# mm8_D016Aoshw.net
KiCad netlist of a schematic drawn in EAGLE
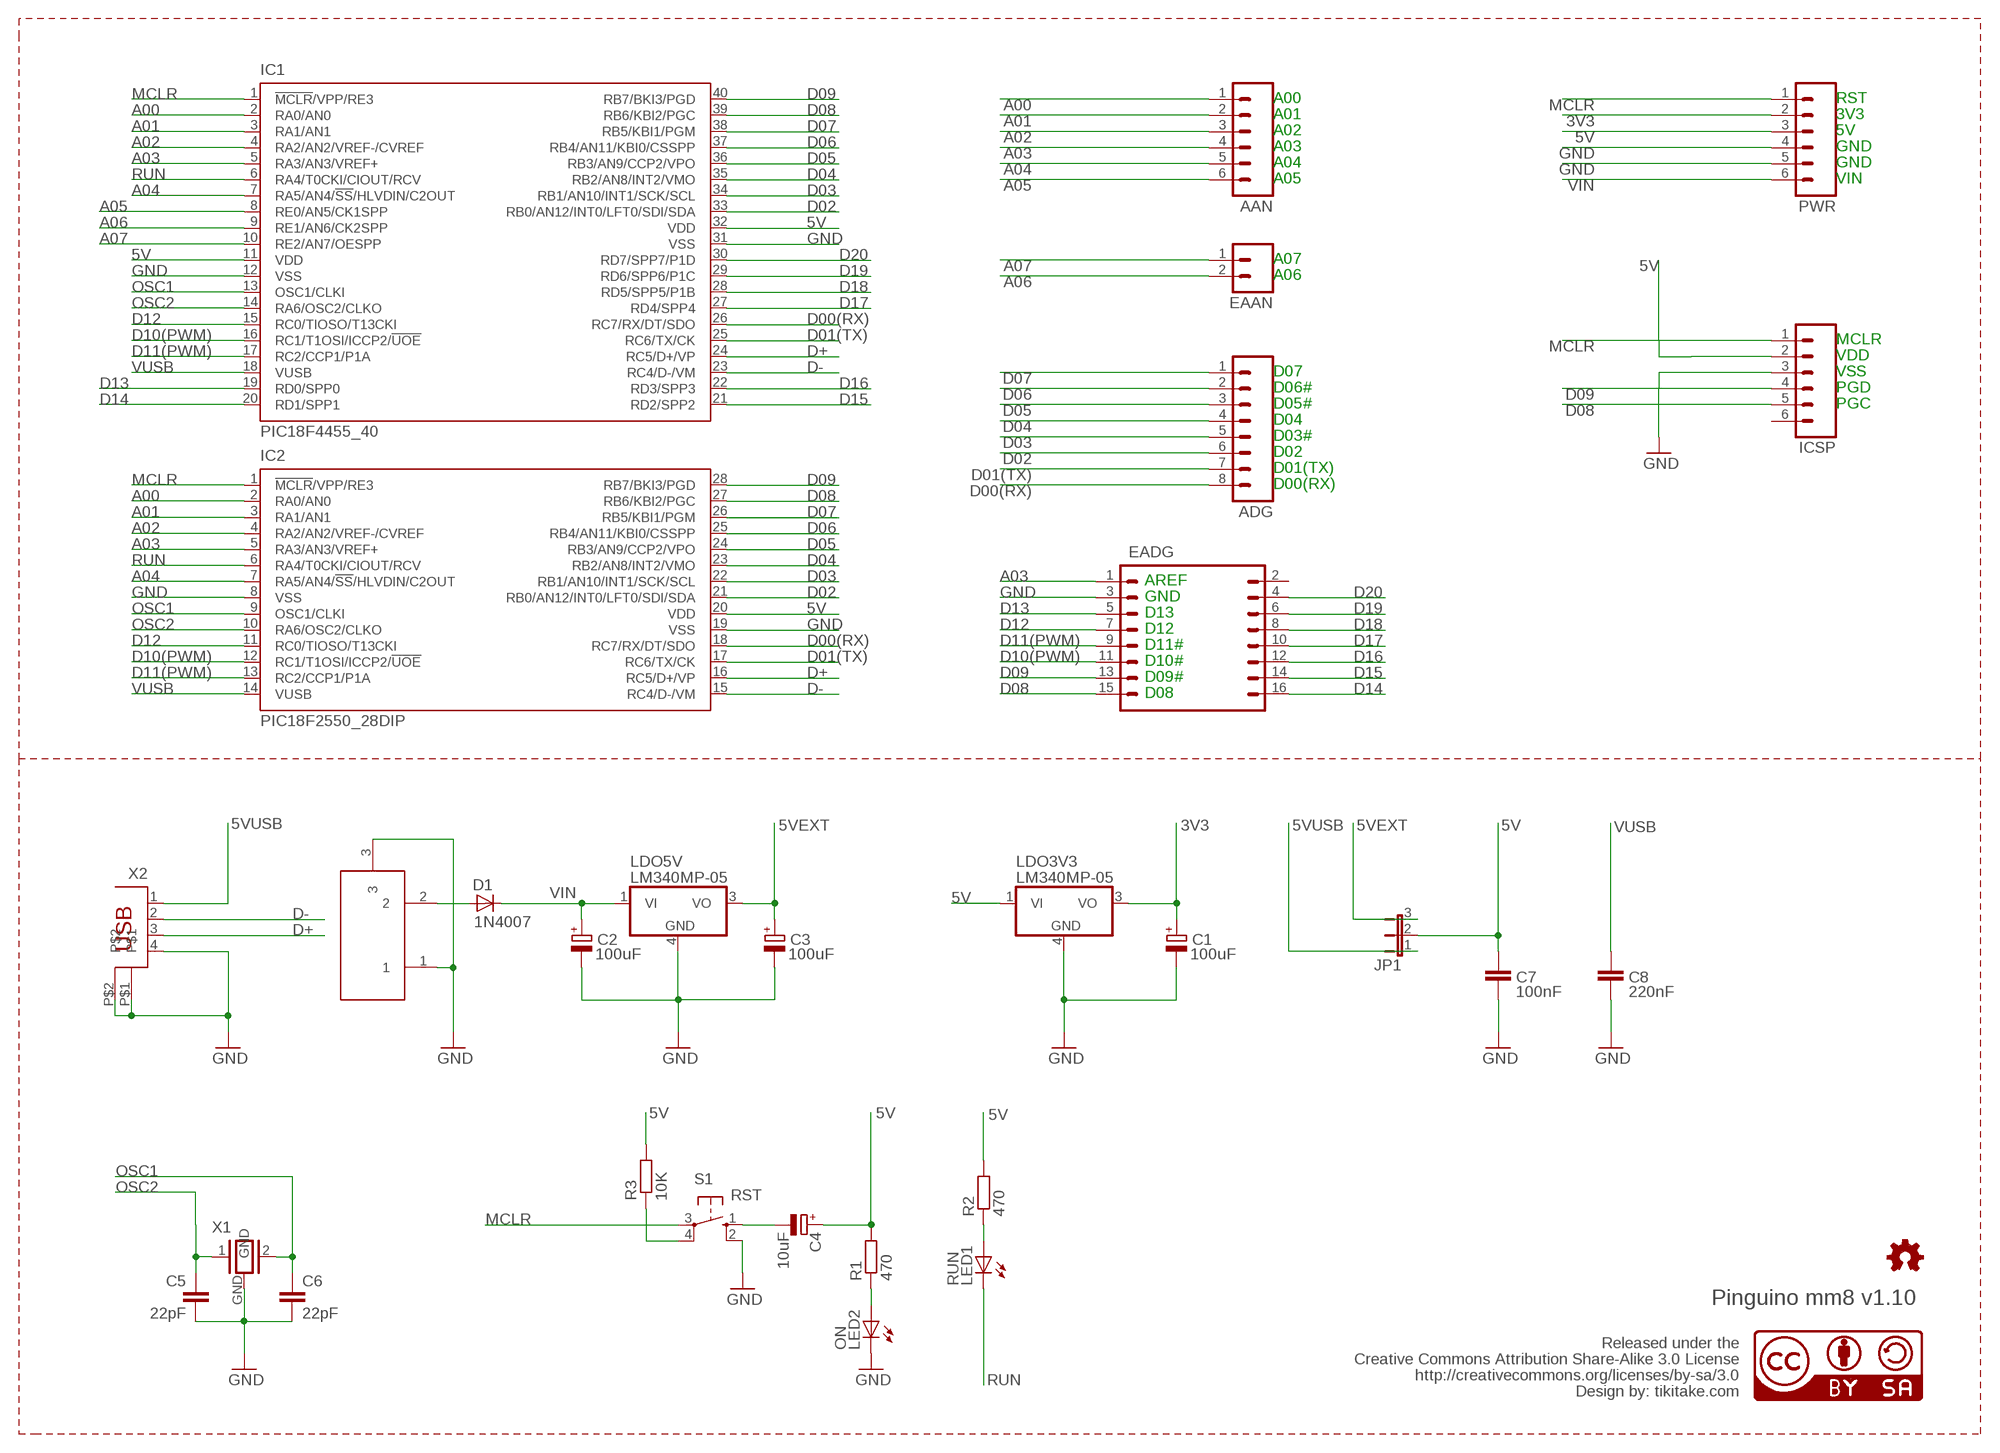
[diagram p0: schematic, sheet 1]

(export (version "E")
  (design (tool "Eeschema 10.0.6"))
  (components
    (comp (ref "AAN")
      (value "M06SIP")
      (footprint "eagle-import:1X06")
      (libsource (lib "eagle-import") (part "M06SIP"))
    )
    (comp (ref "ADG")
      (value "M08")
      (footprint "eagle-import:1X08")
      (libsource (lib "eagle-import") (part "M08"))
    )
    (comp (ref "C1")
      (value "100uF")
      (footprint "eagle-import:E2-5")
      (libsource (lib "eagle-import") (part "CPOL-EUE2-5"))
    )
    (comp (ref "C2")
      (value "100uF")
      (footprint "eagle-import:E2-5")
      (libsource (lib "eagle-import") (part "CPOL-EUE2-5"))
    )
    (comp (ref "C3")
      (value "100uF")
      (footprint "eagle-import:E2-5")
      (libsource (lib "eagle-import") (part "CPOL-EUE2-5"))
    )
    (comp (ref "C4")
      (value "10uF")
      (footprint "eagle-import:E2-5")
      (libsource (lib "eagle-import") (part "n00b0t_004_CPOL-EUE2-5"))
    )
    (comp (ref "C5")
      (value "22pF")
      (footprint "eagle-import:C5B2.5N")
      (libsource (lib "eagle-import") (part "n00b0t_004_C5/2.5N"))
    )
    (comp (ref "C6")
      (value "22pF")
      (footprint "eagle-import:C5B2.5N")
      (libsource (lib "eagle-import") (part "n00b0t_004_C5/2.5N"))
    )
    (comp (ref "C7")
      (value "100nF")
      (footprint "eagle-import:C5B2.5N")
      (libsource (lib "eagle-import") (part "C5/2.5N"))
    )
    (comp (ref "C8")
      (value "220nF")
      (footprint "eagle-import:C5B2.5N")
      (libsource (lib "eagle-import") (part "C5/2.5N"))
    )
    (comp (ref "D1")
      (value "1N4007")
      (footprint "eagle-import:DO41-7")
      (libsource (lib "eagle-import") (part "DIODE7"))
    )
    (comp (ref "EAAN")
      (value "M02PTH")
      (footprint "eagle-import:1X02")
      (libsource (lib "eagle-import") (part "M02PTH"))
    )
    (comp (ref "EADG")
      (value "M08X2")
      (footprint "eagle-import:2X8")
      (libsource (lib "eagle-import") (part "M08X2"))
    )
    (comp (ref "IC1")
      (value "PIC18F4455_40")
      (footprint "eagle-import:DIL40")
      (libsource (lib "eagle-import") (part "PIC18F4_40455"))
    )
    (comp (ref "IC2")
      (value "PIC18F2550_28DIP")
      (footprint "eagle-import:DIL28-3")
      (libsource (lib "eagle-import") (part "PIC18F2_28DIP550"))
    )
    (comp (ref "ICSP")
      (value "M06SIP")
      (footprint "eagle-import:1X06")
      (libsource (lib "eagle-import") (part "M06SIP"))
    )
    (comp (ref "JP1")
      (value "JP2E")
      (footprint "eagle-import:JP2")
      (libsource (lib "eagle-import") (part "JP2E"))
    )
    (comp (ref "LDO3V3")
      (value "LM340MP-05")
      (footprint "eagle-import:SOT223")
      (libsource (lib "eagle-import") (part "LM340?-MP05"))
    )
    (comp (ref "LDO5V")
      (value "LM340MP-05")
      (footprint "eagle-import:SOT223")
      (libsource (lib "eagle-import") (part "LM340?-MP05"))
    )
    (comp (ref "LED1")
      (value "RUN")
      (footprint "eagle-import:LED3MM")
      (libsource (lib "eagle-import") (part "LED3MM"))
    )
    (comp (ref "LED2")
      (value "ON")
      (footprint "eagle-import:LED3MM")
      (libsource (lib "eagle-import") (part "LED3MM"))
    )
    (comp (ref "LOGO1")
      (value "OSHW_LOGO_FILLX0150-NT")
      (footprint "eagle-import:OSHW_FILLX150_NOTEXT")
      (libsource (lib "eagle-import") (part "OSHW_LOGO_FILLX0150-NT"))
    )
    (comp (ref "PWR")
      (value "M06SIP")
      (footprint "eagle-import:1X06")
      (libsource (lib "eagle-import") (part "M06SIP"))
    )
    (comp (ref "R1")
      (value "470")
      (footprint "eagle-import:0207_7")
      (libsource (lib "eagle-import") (part "RESISTOR"))
    )
    (comp (ref "R2")
      (value "470")
      (footprint "eagle-import:0207_7")
      (libsource (lib "eagle-import") (part "RESISTOR"))
    )
    (comp (ref "R3")
      (value "10K")
      (footprint "eagle-import:0207_7")
      (libsource (lib "eagle-import") (part "RESISTOR"))
    )
    (comp (ref "S1")
      (value "RST")
      (footprint "eagle-import:B3F-10XX")
      (libsource (lib "eagle-import") (part "10-XX"))
    )
    (comp (ref "U$3")
      (value "CC-BY-SA")
      (footprint "eagle-import:CC-BY-SA")
      (libsource (lib "eagle-import") (part "CC-BY-SA"))
    )
    (comp (ref "X1")
      (value "RESONATOR")
      (footprint "eagle-import:QS3")
      (libsource (lib "eagle-import") (part "RESONATOR"))
    )
    (comp (ref "X2")
      (value "PN61729")
      (footprint "eagle-import:PN61729")
      (libsource (lib "eagle-import") (part "PN61729"))
    )
    (comp (ref "X4")
      (value "DC21MMX")
      (footprint "eagle-import:DC-21MM")
      (libsource (lib "eagle-import") (part "DC21MMX"))
    )
  )
  (nets
    (net (code "1") (name "/3V3") (class "Default")
      (node (ref "C1") (pin "+") (pinfunction "+_+") (pintype "passive"))
      (node (ref "LDO3V3") (pin "3") (pinfunction "VO_3") (pintype "passive"))
      (node (ref "PWR") (pin "2") (pinfunction "2_2") (pintype "passive"))
    )
    (net (code "2") (name "/5V") (class "Default")
      (node (ref "C4") (pin "+") (pinfunction "+_+") (pintype "passive"))
      (node (ref "C7") (pin "1") (pinfunction "1_1") (pintype "passive"))
      (node (ref "IC1") (pin "11") (pinfunction "VDD_11") (pintype "power_in"))
      (node (ref "IC1") (pin "32") (pinfunction "VDD_32") (pintype "power_in"))
      (node (ref "IC2") (pin "20") (pinfunction "VDD_20") (pintype "power_in"))
      (node (ref "ICSP") (pin "2") (pinfunction "2_2") (pintype "passive"))
      (node (ref "JP1") (pin "2") (pinfunction "2_2") (pintype "passive"))
      (node (ref "LDO3V3") (pin "1") (pinfunction "VI_1") (pintype "input"))
      (node (ref "PWR") (pin "3") (pinfunction "3_3") (pintype "passive"))
      (node (ref "R1") (pin "2") (pinfunction "2_2") (pintype "passive"))
      (node (ref "R2") (pin "2") (pinfunction "2_2") (pintype "passive"))
      (node (ref "R3") (pin "2") (pinfunction "2_2") (pintype "passive"))
    )
    (net (code "3") (name "/5VEXT") (class "Default")
      (node (ref "C3") (pin "+") (pinfunction "+_+") (pintype "passive"))
      (node (ref "JP1") (pin "3") (pinfunction "3_3") (pintype "passive"))
      (node (ref "LDO5V") (pin "3") (pinfunction "VO_3") (pintype "passive"))
    )
    (net (code "4") (name "/5VUSB") (class "Default")
      (node (ref "JP1") (pin "1") (pinfunction "1_1") (pintype "passive"))
      (node (ref "X2") (pin "1") (pinfunction "1_1") (pintype "bidirectional"))
    )
    (net (code "5") (name "/A00") (class "Default")
      (node (ref "AAN") (pin "1") (pinfunction "1_1") (pintype "passive"))
      (node (ref "IC1") (pin "2") (pinfunction "RA0/AN0_2") (pintype "bidirectional"))
      (node (ref "IC2") (pin "2") (pinfunction "RA0/AN0_2") (pintype "bidirectional"))
    )
    (net (code "6") (name "/A01") (class "Default")
      (node (ref "AAN") (pin "2") (pinfunction "2_2") (pintype "passive"))
      (node (ref "IC1") (pin "3") (pinfunction "RA1/AN1_3") (pintype "bidirectional"))
      (node (ref "IC2") (pin "3") (pinfunction "RA1/AN1_3") (pintype "bidirectional"))
    )
    (net (code "7") (name "/A02") (class "Default")
      (node (ref "AAN") (pin "3") (pinfunction "3_3") (pintype "passive"))
      (node (ref "IC1") (pin "4") (pinfunction "RA2/AN2/VREF-/CVREF_4") (pintype "bidirectional"))
      (node (ref "IC2") (pin "4") (pinfunction "RA2/AN2/VREF-/CVREF_4") (pintype "bidirectional"))
    )
    (net (code "8") (name "/A03") (class "Default")
      (node (ref "AAN") (pin "4") (pinfunction "4_4") (pintype "passive"))
      (node (ref "EADG") (pin "1") (pinfunction "1_1") (pintype "passive"))
      (node (ref "IC1") (pin "5") (pinfunction "RA3/AN3/VREF+_5") (pintype "bidirectional"))
      (node (ref "IC2") (pin "5") (pinfunction "RA3/AN3/VREF+_5") (pintype "bidirectional"))
    )
    (net (code "9") (name "/A04") (class "Default")
      (node (ref "AAN") (pin "5") (pinfunction "5_5") (pintype "passive"))
      (node (ref "IC1") (pin "7") (pinfunction "RA5/AN4/~{SS}/HLVDIN/C2OUT_7") (pintype "bidirectional"))
      (node (ref "IC2") (pin "7") (pinfunction "RA5/AN4/~{SS}/HLVDIN/C2OUT_7") (pintype "bidirectional"))
    )
    (net (code "10") (name "/A05") (class "Default")
      (node (ref "AAN") (pin "6") (pinfunction "6_6") (pintype "passive"))
      (node (ref "IC1") (pin "8") (pinfunction "RE0/AN5/CK1SPP_8") (pintype "bidirectional"))
    )
    (net (code "11") (name "/A06") (class "Default")
      (node (ref "EAAN") (pin "2") (pinfunction "2_2") (pintype "passive"))
      (node (ref "IC1") (pin "9") (pinfunction "RE1/AN6/CK2SPP_9") (pintype "bidirectional"))
    )
    (net (code "12") (name "/A07") (class "Default")
      (node (ref "EAAN") (pin "1") (pinfunction "1_1") (pintype "passive"))
      (node (ref "IC1") (pin "10") (pinfunction "RE2/AN7/OESPP_10") (pintype "bidirectional"))
    )
    (net (code "13") (name "/D+") (class "Default")
      (node (ref "IC1") (pin "24") (pinfunction "RC5/D+/VP_24") (pintype "bidirectional"))
      (node (ref "IC2") (pin "16") (pinfunction "RC5/D+/VP_16") (pintype "bidirectional"))
      (node (ref "X2") (pin "3") (pinfunction "3_3") (pintype "bidirectional"))
    )
    (net (code "14") (name "/D-") (class "Default")
      (node (ref "IC1") (pin "23") (pinfunction "RC4/D-/VM_23") (pintype "bidirectional"))
      (node (ref "IC2") (pin "15") (pinfunction "RC4/D-/VM_15") (pintype "bidirectional"))
      (node (ref "X2") (pin "2") (pinfunction "2_2") (pintype "bidirectional"))
    )
    (net (code "15") (name "/D00(RX)") (class "Default")
      (node (ref "ADG") (pin "8") (pinfunction "8_8") (pintype "passive"))
      (node (ref "IC1") (pin "26") (pinfunction "RC7/RX/DT/SDO_26") (pintype "bidirectional"))
      (node (ref "IC2") (pin "18") (pinfunction "RC7/RX/DT/SDO_18") (pintype "bidirectional"))
    )
    (net (code "16") (name "/D01(TX)") (class "Default")
      (node (ref "ADG") (pin "7") (pinfunction "7_7") (pintype "passive"))
      (node (ref "IC1") (pin "25") (pinfunction "RC6/TX/CK_25") (pintype "bidirectional"))
      (node (ref "IC2") (pin "17") (pinfunction "RC6/TX/CK_17") (pintype "bidirectional"))
    )
    (net (code "17") (name "/D02") (class "Default")
      (node (ref "ADG") (pin "6") (pinfunction "6_6") (pintype "passive"))
      (node (ref "IC1") (pin "33") (pinfunction "RB0/AN12/INT0/LFT0/SDI/SDA_33") (pintype "bidirectional"))
      (node (ref "IC2") (pin "21") (pinfunction "RB0/AN12/INT0/LFT0/SDI/SDA_21") (pintype "bidirectional"))
    )
    (net (code "18") (name "/D03") (class "Default")
      (node (ref "ADG") (pin "5") (pinfunction "5_5") (pintype "passive"))
      (node (ref "IC1") (pin "34") (pinfunction "RB1/AN10/INT1/SCK/SCL_34") (pintype "bidirectional"))
      (node (ref "IC2") (pin "22") (pinfunction "RB1/AN10/INT1/SCK/SCL_22") (pintype "bidirectional"))
    )
    (net (code "19") (name "/D04") (class "Default")
      (node (ref "ADG") (pin "4") (pinfunction "4_4") (pintype "passive"))
      (node (ref "IC1") (pin "35") (pinfunction "RB2/AN8/INT2/VMO_35") (pintype "bidirectional"))
      (node (ref "IC2") (pin "23") (pinfunction "RB2/AN8/INT2/VMO_23") (pintype "bidirectional"))
    )
    (net (code "20") (name "/D05") (class "Default")
      (node (ref "ADG") (pin "3") (pinfunction "3_3") (pintype "passive"))
      (node (ref "IC1") (pin "36") (pinfunction "RB3/AN9/CCP2/VPO_36") (pintype "bidirectional"))
      (node (ref "IC2") (pin "24") (pinfunction "RB3/AN9/CCP2/VPO_24") (pintype "bidirectional"))
    )
    (net (code "21") (name "/D06") (class "Default")
      (node (ref "ADG") (pin "2") (pinfunction "2_2") (pintype "passive"))
      (node (ref "IC1") (pin "37") (pinfunction "RB4/AN11/KBI0/CSSPP_37") (pintype "bidirectional"))
      (node (ref "IC2") (pin "25") (pinfunction "RB4/AN11/KBI0/CSSPP_25") (pintype "bidirectional"))
    )
    (net (code "22") (name "/D07") (class "Default")
      (node (ref "ADG") (pin "1") (pinfunction "1_1") (pintype "passive"))
      (node (ref "IC1") (pin "38") (pinfunction "RB5/KBI1/PGM_38") (pintype "bidirectional"))
      (node (ref "IC2") (pin "26") (pinfunction "RB5/KBI1/PGM_26") (pintype "bidirectional"))
    )
    (net (code "23") (name "/D08") (class "Default")
      (node (ref "EADG") (pin "15") (pinfunction "15_15") (pintype "passive"))
      (node (ref "IC1") (pin "39") (pinfunction "RB6/KBI2/PGC_39") (pintype "bidirectional"))
      (node (ref "IC2") (pin "27") (pinfunction "RB6/KBI2/PGC_27") (pintype "bidirectional"))
      (node (ref "ICSP") (pin "5") (pinfunction "5_5") (pintype "passive"))
    )
    (net (code "24") (name "/D09") (class "Default")
      (node (ref "EADG") (pin "13") (pinfunction "13_13") (pintype "passive"))
      (node (ref "IC1") (pin "40") (pinfunction "RB7/BKI3/PGD_40") (pintype "bidirectional"))
      (node (ref "IC2") (pin "28") (pinfunction "RB7/BKI3/PGD_28") (pintype "bidirectional"))
      (node (ref "ICSP") (pin "4") (pinfunction "4_4") (pintype "passive"))
    )
    (net (code "25") (name "/D10(PWM)") (class "Default")
      (node (ref "EADG") (pin "11") (pinfunction "11_11") (pintype "passive"))
      (node (ref "IC1") (pin "16") (pinfunction "RC1/T1OSI/ICCP2/~{UOE}_16") (pintype "bidirectional"))
      (node (ref "IC2") (pin "12") (pinfunction "RC1/T1OSI/ICCP2/~{UOE}_12") (pintype "bidirectional"))
    )
    (net (code "26") (name "/D11(PWM)") (class "Default")
      (node (ref "EADG") (pin "9") (pinfunction "9_9") (pintype "passive"))
      (node (ref "IC1") (pin "17") (pinfunction "RC2/CCP1/P1A_17") (pintype "bidirectional"))
      (node (ref "IC2") (pin "13") (pinfunction "RC2/CCP1/P1A_13") (pintype "bidirectional"))
    )
    (net (code "27") (name "/D12") (class "Default")
      (node (ref "EADG") (pin "7") (pinfunction "7_7") (pintype "passive"))
      (node (ref "IC1") (pin "15") (pinfunction "RC0/TIOSO/T13CKI_15") (pintype "bidirectional"))
      (node (ref "IC2") (pin "11") (pinfunction "RC0/TIOSO/T13CKI_11") (pintype "bidirectional"))
    )
    (net (code "28") (name "/D13") (class "Default")
      (node (ref "EADG") (pin "5") (pinfunction "5_5") (pintype "passive"))
      (node (ref "IC1") (pin "19") (pinfunction "RD0/SPP0_19") (pintype "bidirectional"))
    )
    (net (code "29") (name "/D14") (class "Default")
      (node (ref "EADG") (pin "16") (pinfunction "16_16") (pintype "passive"))
      (node (ref "IC1") (pin "20") (pinfunction "RD1/SPP1_20") (pintype "bidirectional"))
    )
    (net (code "30") (name "/D15") (class "Default")
      (node (ref "EADG") (pin "14") (pinfunction "14_14") (pintype "passive"))
      (node (ref "IC1") (pin "21") (pinfunction "RD2/SPP2_21") (pintype "bidirectional"))
    )
    (net (code "31") (name "/D16") (class "Default")
      (node (ref "EADG") (pin "12") (pinfunction "12_12") (pintype "passive"))
      (node (ref "IC1") (pin "22") (pinfunction "RD3/SPP3_22") (pintype "bidirectional"))
    )
    (net (code "32") (name "/D17") (class "Default")
      (node (ref "EADG") (pin "10") (pinfunction "10_10") (pintype "passive"))
      (node (ref "IC1") (pin "27") (pinfunction "RD4/SPP4_27") (pintype "bidirectional"))
    )
    (net (code "33") (name "/D18") (class "Default")
      (node (ref "EADG") (pin "8") (pinfunction "8_8") (pintype "passive"))
      (node (ref "IC1") (pin "28") (pinfunction "RD5/SPP5/P1B_28") (pintype "bidirectional"))
    )
    (net (code "34") (name "/D19") (class "Default")
      (node (ref "EADG") (pin "6") (pinfunction "6_6") (pintype "passive"))
      (node (ref "IC1") (pin "29") (pinfunction "RD6/SPP6/P1C_29") (pintype "bidirectional"))
    )
    (net (code "35") (name "/D20") (class "Default")
      (node (ref "EADG") (pin "4") (pinfunction "4_4") (pintype "passive"))
      (node (ref "IC1") (pin "30") (pinfunction "RD7/SPP7/P1D_30") (pintype "bidirectional"))
    )
    (net (code "36") (name "/MCLR") (class "Default")
      (node (ref "IC1") (pin "1") (pinfunction "~{MCLR}/VPP/RE3_1") (pintype "input"))
      (node (ref "IC2") (pin "1") (pinfunction "~{MCLR}/VPP/RE3_1") (pintype "input"))
      (node (ref "ICSP") (pin "1") (pinfunction "1_1") (pintype "passive"))
      (node (ref "PWR") (pin "1") (pinfunction "1_1") (pintype "passive"))
      (node (ref "S1") (pin "3") (pinfunction "P_3") (pintype "passive"))
    )
    (net (code "37") (name "/OSC1") (class "Default")
      (node (ref "C6") (pin "1") (pinfunction "1_1") (pintype "passive"))
      (node (ref "IC1") (pin "13") (pinfunction "OSC1/CLKI_13") (pintype "input"))
      (node (ref "IC2") (pin "9") (pinfunction "OSC1/CLKI_9") (pintype "input"))
      (node (ref "X1") (pin "2") (pinfunction "2_2") (pintype "passive"))
    )
    (net (code "38") (name "/OSC2") (class "Default")
      (node (ref "C5") (pin "1") (pinfunction "1_1") (pintype "passive"))
      (node (ref "IC1") (pin "14") (pinfunction "RA6/OSC2/CLKO_14") (pintype "output"))
      (node (ref "IC2") (pin "10") (pinfunction "RA6/OSC2/CLKO_10") (pintype "output"))
      (node (ref "X1") (pin "1") (pinfunction "1_1") (pintype "passive"))
    )
    (net (code "39") (name "/RUN") (class "Default")
      (node (ref "IC1") (pin "6") (pinfunction "RA4/T0CKI/CIOUT/RCV_6") (pintype "bidirectional"))
      (node (ref "IC2") (pin "6") (pinfunction "RA4/T0CKI/CIOUT/RCV_6") (pintype "bidirectional"))
      (node (ref "LED1") (pin "K") (pinfunction "C_K") (pintype "passive"))
    )
    (net (code "40") (name "/VIN") (class "Default")
      (node (ref "C2") (pin "+") (pinfunction "+_+") (pintype "passive"))
      (node (ref "D1") (pin "C") (pinfunction "C_C") (pintype "passive"))
      (node (ref "LDO5V") (pin "1") (pinfunction "VI_1") (pintype "input"))
      (node (ref "PWR") (pin "6") (pinfunction "6_6") (pintype "passive"))
    )
    (net (code "41") (name "/VUSB") (class "Default")
      (node (ref "C8") (pin "1") (pinfunction "1_1") (pintype "passive"))
      (node (ref "IC1") (pin "18") (pinfunction "VUSB_18") (pintype "bidirectional"))
      (node (ref "IC2") (pin "14") (pinfunction "VUSB_14") (pintype "bidirectional"))
    )
    (net (code "42") (name "GND") (class "Default")
      (node (ref "C1") (pin "-") (pinfunction "-_-") (pintype "passive"))
      (node (ref "C2") (pin "-") (pinfunction "-_-") (pintype "passive"))
      (node (ref "C3") (pin "-") (pinfunction "-_-") (pintype "passive"))
      (node (ref "C5") (pin "2") (pinfunction "2_2") (pintype "passive"))
      (node (ref "C6") (pin "2") (pinfunction "2_2") (pintype "passive"))
      (node (ref "C7") (pin "2") (pinfunction "2_2") (pintype "passive"))
      (node (ref "C8") (pin "2") (pinfunction "2_2") (pintype "passive"))
      (node (ref "EADG") (pin "3") (pinfunction "3_3") (pintype "passive"))
      (node (ref "IC1") (pin "12") (pinfunction "VSS_12") (pintype "power_in"))
      (node (ref "IC1") (pin "31") (pinfunction "VSS_31") (pintype "power_in"))
      (node (ref "IC2") (pin "19") (pinfunction "VSS_19") (pintype "power_in"))
      (node (ref "IC2") (pin "8") (pinfunction "VSS_8") (pintype "power_in"))
      (node (ref "ICSP") (pin "3") (pinfunction "3_3") (pintype "passive"))
      (node (ref "LDO3V3") (pin "4") (pinfunction "GND_4") (pintype "passive"))
      (node (ref "LDO5V") (pin "4") (pinfunction "GND_4") (pintype "passive"))
      (node (ref "LED2") (pin "K") (pinfunction "C_K") (pintype "passive"))
      (node (ref "PWR") (pin "4") (pinfunction "4_4") (pintype "passive"))
      (node (ref "PWR") (pin "5") (pinfunction "5_5") (pintype "passive"))
      (node (ref "S1") (pin "2") (pinfunction "S1_2") (pintype "passive"))
      (node (ref "X1") (pin "GND") (pinfunction "GND_GND") (pintype "power_in"))
      (node (ref "X2") (pin "4") (pinfunction "4_4") (pintype "bidirectional"))
      (node (ref "X2") (pin "P$1") (pinfunction "P$1_P$1") (pintype "bidirectional"))
      (node (ref "X2") (pin "P$2") (pinfunction "P$2_P$2") (pintype "bidirectional"))
      (node (ref "X4") (pin "1") (pinfunction "1_1") (pintype "power_in"))
      (node (ref "X4") (pin "3") (pinfunction "3_3") (pintype "power_in"))
    )
    (net (code "43") (name "Net-(D1-PadA)") (class "Default")
      (node (ref "D1") (pin "A") (pinfunction "A_A") (pintype "passive"))
      (node (ref "X4") (pin "2") (pinfunction "2_2") (pintype "power_in"))
    )
    (net (code "44") (name "Net-(LED1-PadA)") (class "Default")
      (node (ref "LED1") (pin "A") (pinfunction "A_A") (pintype "passive"))
      (node (ref "R2") (pin "1") (pinfunction "1_1") (pintype "passive"))
    )
    (net (code "45") (name "Net-(LED2-PadA)") (class "Default")
      (node (ref "LED2") (pin "A") (pinfunction "A_A") (pintype "passive"))
      (node (ref "R1") (pin "1") (pinfunction "1_1") (pintype "passive"))
    )
    (net (code "46") (name "Net-(S1-P1)") (class "Default")
      (node (ref "R3") (pin "1") (pinfunction "1_1") (pintype "passive"))
      (node (ref "S1") (pin "4") (pinfunction "P1_4") (pintype "passive"))
    )
    (net (code "47") (name "Net-(S1-S)") (class "Default")
      (node (ref "C4") (pin "-") (pinfunction "-_-") (pintype "passive"))
      (node (ref "S1") (pin "1") (pinfunction "S_1") (pintype "passive"))
    )
    (net (code "48") (name "unconnected-(EADG-Pad2)") (class "Default")
      (node (ref "EADG") (pin "2") (pinfunction "2_2") (pintype "passive"))
    )
    (net (code "49") (name "unconnected-(ICSP-Pad6)") (class "Default")
      (node (ref "ICSP") (pin "6") (pinfunction "6_6") (pintype "passive"))
    )
  )
)
